# Dual_H-bridge1.net
KiCad netlist of a schematic drawn in EAGLE
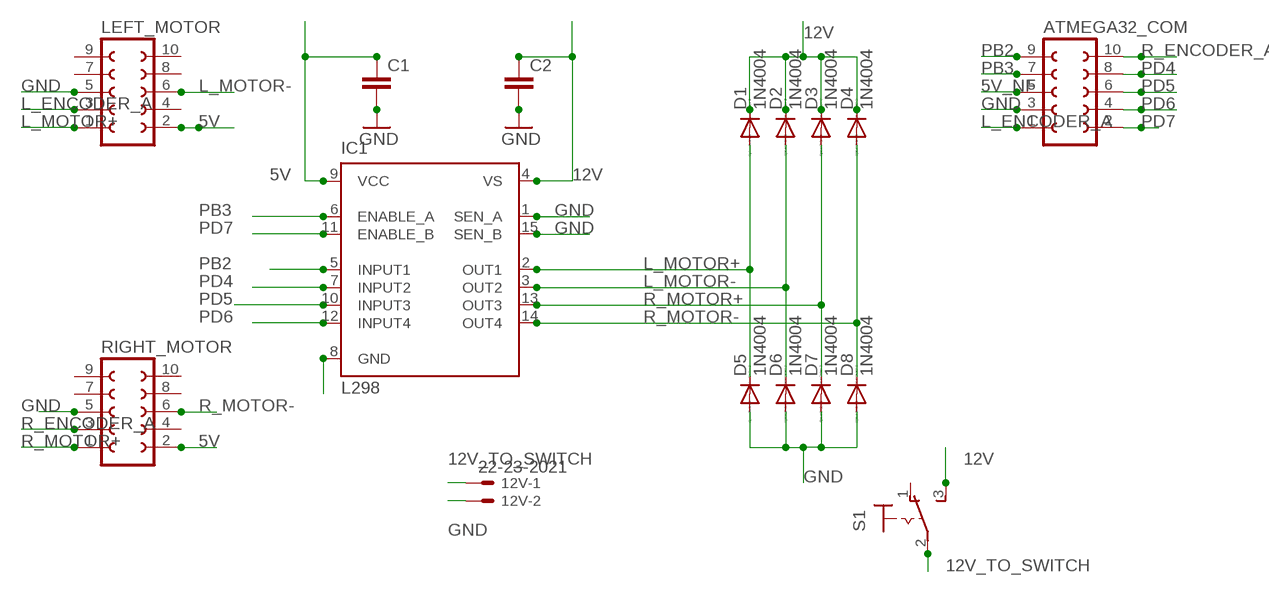
[diagram p0: schematic, sheet 1]

(export (version "E")
  (design (tool "Eeschema 10.0.6"))
  (components
    (comp (ref "12V")
      (value "22-23-2021")
      (footprint "eagle-import:22-23-2021")
      (fields (field (name "MF") "MOLEX"))
      (libsource (lib "eagle-import") (part "22-23-2021"))
    )
    (comp (ref "ATMEGA32_COM")
      (value "FE05-2")
      (footprint "eagle-import:FE05-2")
      (libsource (lib "eagle-import") (part "FE05-2"))
    )
    (comp (ref "C1")
      (value "C5/3")
      (footprint "eagle-import:C5B3")
      (libsource (lib "eagle-import") (part "C5/3"))
    )
    (comp (ref "C2")
      (value "C5/3")
      (footprint "eagle-import:C5B3")
      (libsource (lib "eagle-import") (part "C5/3"))
    )
    (comp (ref "D1")
      (value "1N4004")
      (footprint "eagle-import:DO41-10")
      (libsource (lib "eagle-import") (part "1N4004"))
    )
    (comp (ref "D2")
      (value "1N4004")
      (footprint "eagle-import:DO41-10")
      (libsource (lib "eagle-import") (part "1N4004"))
    )
    (comp (ref "D3")
      (value "1N4004")
      (footprint "eagle-import:DO41-10")
      (libsource (lib "eagle-import") (part "1N4004"))
    )
    (comp (ref "D4")
      (value "1N4004")
      (footprint "eagle-import:DO41-10")
      (libsource (lib "eagle-import") (part "1N4004"))
    )
    (comp (ref "D5")
      (value "1N4004")
      (footprint "eagle-import:DO41-10")
      (libsource (lib "eagle-import") (part "1N4004"))
    )
    (comp (ref "D6")
      (value "1N4004")
      (footprint "eagle-import:DO41-10")
      (libsource (lib "eagle-import") (part "1N4004"))
    )
    (comp (ref "D7")
      (value "1N4004")
      (footprint "eagle-import:DO41-10")
      (libsource (lib "eagle-import") (part "1N4004"))
    )
    (comp (ref "D8")
      (value "1N4004")
      (footprint "eagle-import:DO41-10")
      (libsource (lib "eagle-import") (part "1N4004"))
    )
    (comp (ref "IC1")
      (value "L298")
      (footprint "eagle-import:MULTIWATT-15")
      (fields (field (name "MPN") "L298N"))
      (libsource (lib "eagle-import") (part "L298"))
    )
    (comp (ref "LEFT_MOTOR")
      (value "FE05-2")
      (footprint "eagle-import:FE05-2")
      (libsource (lib "eagle-import") (part "FE05-2"))
    )
    (comp (ref "RIGHT_MOTOR")
      (value "FE05-2")
      (footprint "eagle-import:FE05-2")
      (libsource (lib "eagle-import") (part "FE05-2"))
    )
    (comp (ref "S1")
      (value "M9040P")
      (footprint "eagle-import:M9040P")
      (libsource (lib "eagle-import") (part "M9040P"))
    )
  )
  (nets
    (net (code "1") (name "/5V") (class "Default")
      (node (ref "C1") (pin "1") (pinfunction "1_1") (pintype "passive"))
      (node (ref "IC1") (pin "9") (pinfunction "VCC_9") (pintype "power_in"))
      (node (ref "LEFT_MOTOR") (pin "2") (pinfunction "2_2") (pintype "passive"))
      (node (ref "RIGHT_MOTOR") (pin "2") (pinfunction "2_2") (pintype "passive"))
    )
    (net (code "2") (name "/5V_NF") (class "Default")
      (node (ref "ATMEGA32_COM") (pin "5") (pinfunction "5_5") (pintype "passive"))
    )
    (net (code "3") (name "/12V") (class "Default")
      (node (ref "C2") (pin "1") (pinfunction "1_1") (pintype "passive"))
      (node (ref "D1") (pin "C") (pinfunction "C_C") (pintype "passive"))
      (node (ref "D2") (pin "C") (pinfunction "C_C") (pintype "passive"))
      (node (ref "D3") (pin "C") (pinfunction "C_C") (pintype "passive"))
      (node (ref "D4") (pin "C") (pinfunction "C_C") (pintype "passive"))
      (node (ref "IC1") (pin "4") (pinfunction "VS_4") (pintype "power_in"))
      (node (ref "S1") (pin "3") (pinfunction "S_3") (pintype "passive"))
    )
    (net (code "4") (name "/12V_TO_SWITCH") (class "Default")
      (node (ref "12V") (pin "1") (pinfunction "S_1") (pintype "passive"))
      (node (ref "S1") (pin "2") (pinfunction "P_2") (pintype "passive"))
    )
    (net (code "5") (name "/L_ENCODER_A") (class "Default")
      (node (ref "ATMEGA32_COM") (pin "1") (pinfunction "1_1") (pintype "passive"))
      (node (ref "LEFT_MOTOR") (pin "3") (pinfunction "3_3") (pintype "passive"))
    )
    (net (code "6") (name "/L_MOTOR+") (class "Default")
      (node (ref "D1") (pin "A") (pinfunction "A_A") (pintype "passive"))
      (node (ref "D5") (pin "C") (pinfunction "C_C") (pintype "passive"))
      (node (ref "IC1") (pin "2") (pinfunction "OUT1_2") (pintype "output"))
      (node (ref "LEFT_MOTOR") (pin "1") (pinfunction "1_1") (pintype "passive"))
    )
    (net (code "7") (name "/L_MOTOR-") (class "Default")
      (node (ref "D2") (pin "A") (pinfunction "A_A") (pintype "passive"))
      (node (ref "D6") (pin "C") (pinfunction "C_C") (pintype "passive"))
      (node (ref "IC1") (pin "3") (pinfunction "OUT2_3") (pintype "output"))
      (node (ref "LEFT_MOTOR") (pin "6") (pinfunction "6_6") (pintype "passive"))
    )
    (net (code "8") (name "/PB2") (class "Default")
      (node (ref "ATMEGA32_COM") (pin "9") (pinfunction "9_9") (pintype "passive"))
      (node (ref "IC1") (pin "5") (pinfunction "INPUT1_5") (pintype "input"))
    )
    (net (code "9") (name "/PB3") (class "Default")
      (node (ref "ATMEGA32_COM") (pin "7") (pinfunction "7_7") (pintype "passive"))
      (node (ref "IC1") (pin "6") (pinfunction "ENABLE_A_6") (pintype "input"))
    )
    (net (code "10") (name "/PD4") (class "Default")
      (node (ref "ATMEGA32_COM") (pin "8") (pinfunction "8_8") (pintype "passive"))
      (node (ref "IC1") (pin "7") (pinfunction "INPUT2_7") (pintype "input"))
    )
    (net (code "11") (name "/PD5") (class "Default")
      (node (ref "ATMEGA32_COM") (pin "6") (pinfunction "6_6") (pintype "passive"))
      (node (ref "IC1") (pin "10") (pinfunction "INPUT3_10") (pintype "input"))
    )
    (net (code "12") (name "/PD6") (class "Default")
      (node (ref "ATMEGA32_COM") (pin "4") (pinfunction "4_4") (pintype "passive"))
      (node (ref "IC1") (pin "12") (pinfunction "INPUT4_12") (pintype "input"))
    )
    (net (code "13") (name "/PD7") (class "Default")
      (node (ref "ATMEGA32_COM") (pin "2") (pinfunction "2_2") (pintype "passive"))
      (node (ref "IC1") (pin "11") (pinfunction "ENABLE_B_11") (pintype "input"))
    )
    (net (code "14") (name "/R_ENCODER_A") (class "Default")
      (node (ref "ATMEGA32_COM") (pin "10") (pinfunction "10_10") (pintype "passive"))
      (node (ref "RIGHT_MOTOR") (pin "3") (pinfunction "3_3") (pintype "passive"))
    )
    (net (code "15") (name "/R_MOTOR+") (class "Default")
      (node (ref "D3") (pin "A") (pinfunction "A_A") (pintype "passive"))
      (node (ref "D7") (pin "C") (pinfunction "C_C") (pintype "passive"))
      (node (ref "IC1") (pin "13") (pinfunction "OUT3_13") (pintype "output"))
      (node (ref "RIGHT_MOTOR") (pin "1") (pinfunction "1_1") (pintype "passive"))
    )
    (net (code "16") (name "/R_MOTOR-") (class "Default")
      (node (ref "D4") (pin "A") (pinfunction "A_A") (pintype "passive"))
      (node (ref "D8") (pin "C") (pinfunction "C_C") (pintype "passive"))
      (node (ref "IC1") (pin "14") (pinfunction "OUT4_14") (pintype "output"))
      (node (ref "RIGHT_MOTOR") (pin "6") (pinfunction "6_6") (pintype "passive"))
    )
    (net (code "17") (name "GND") (class "Default")
      (node (ref "12V") (pin "2") (pinfunction "S_2") (pintype "passive"))
      (node (ref "ATMEGA32_COM") (pin "3") (pinfunction "3_3") (pintype "passive"))
      (node (ref "C1") (pin "2") (pinfunction "2_2") (pintype "passive"))
      (node (ref "C2") (pin "2") (pinfunction "2_2") (pintype "passive"))
      (node (ref "D5") (pin "A") (pinfunction "A_A") (pintype "passive"))
      (node (ref "D6") (pin "A") (pinfunction "A_A") (pintype "passive"))
      (node (ref "D7") (pin "A") (pinfunction "A_A") (pintype "passive"))
      (node (ref "D8") (pin "A") (pinfunction "A_A") (pintype "passive"))
      (node (ref "IC1") (pin "1") (pinfunction "SEN_A_1") (pintype "input"))
      (node (ref "IC1") (pin "15") (pinfunction "SEN_B_15") (pintype "input"))
      (node (ref "IC1") (pin "8") (pinfunction "GND_8") (pintype "power_in"))
      (node (ref "LEFT_MOTOR") (pin "5") (pinfunction "5_5") (pintype "passive"))
      (node (ref "RIGHT_MOTOR") (pin "5") (pinfunction "5_5") (pintype "passive"))
    )
    (net (code "18") (name "unconnected-(LEFT_MOTOR-Pad4)") (class "Default")
      (node (ref "LEFT_MOTOR") (pin "4") (pinfunction "4_4") (pintype "passive"))
    )
    (net (code "19") (name "unconnected-(LEFT_MOTOR-Pad7)") (class "Default")
      (node (ref "LEFT_MOTOR") (pin "7") (pinfunction "7_7") (pintype "passive"))
    )
    (net (code "20") (name "unconnected-(LEFT_MOTOR-Pad8)") (class "Default")
      (node (ref "LEFT_MOTOR") (pin "8") (pinfunction "8_8") (pintype "passive"))
    )
    (net (code "21") (name "unconnected-(LEFT_MOTOR-Pad9)") (class "Default")
      (node (ref "LEFT_MOTOR") (pin "9") (pinfunction "9_9") (pintype "passive"))
    )
    (net (code "22") (name "unconnected-(LEFT_MOTOR-Pad10)") (class "Default")
      (node (ref "LEFT_MOTOR") (pin "10") (pinfunction "10_10") (pintype "passive"))
    )
    (net (code "23") (name "unconnected-(RIGHT_MOTOR-Pad4)") (class "Default")
      (node (ref "RIGHT_MOTOR") (pin "4") (pinfunction "4_4") (pintype "passive"))
    )
    (net (code "24") (name "unconnected-(RIGHT_MOTOR-Pad7)") (class "Default")
      (node (ref "RIGHT_MOTOR") (pin "7") (pinfunction "7_7") (pintype "passive"))
    )
    (net (code "25") (name "unconnected-(RIGHT_MOTOR-Pad8)") (class "Default")
      (node (ref "RIGHT_MOTOR") (pin "8") (pinfunction "8_8") (pintype "passive"))
    )
    (net (code "26") (name "unconnected-(RIGHT_MOTOR-Pad9)") (class "Default")
      (node (ref "RIGHT_MOTOR") (pin "9") (pinfunction "9_9") (pintype "passive"))
    )
    (net (code "27") (name "unconnected-(RIGHT_MOTOR-Pad10)") (class "Default")
      (node (ref "RIGHT_MOTOR") (pin "10") (pinfunction "10_10") (pintype "passive"))
    )
    (net (code "28") (name "unconnected-(S1-O-Pad1)") (class "Default")
      (node (ref "S1") (pin "1") (pinfunction "O_1") (pintype "passive"))
    )
  )
)
